# q1.net
KiCad netlist of a schematic drawn in EAGLE
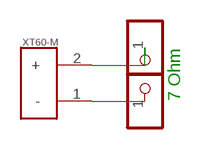
[diagram p0: schematic, sheet 1]

(export (version "E")
  (design (tool "Eeschema 10.0.6"))
  (components
    (comp (ref "J1")
      (value "XT60-M")
      (footprint "eagle-import:AMASS_XT60-M")
      (fields (field (name "MF") "AMASS"))
      (libsource (lib "eagle-import") (part "XT60-M"))
    )
    (comp (ref "JP1")
      (value "PINHD-1X1")
      (footprint "eagle-import:1X01")
      (libsource (lib "eagle-import") (part "PINHD-1X1"))
    )
    (comp (ref "JP2")
      (value "PINHD-1X1")
      (footprint "eagle-import:1X01")
      (libsource (lib "eagle-import") (part "PINHD-1X1"))
    )
  )
  (nets
    (net (code "1") (name "Net-(J1-+)") (class "Default")
      (node (ref "J1") (pin "2") (pinfunction "+_2") (pintype "passive"))
      (node (ref "JP1") (pin "1") (pinfunction "1_1") (pintype "passive"))
    )
    (net (code "2") (name "Net-(J1--)") (class "Default")
      (node (ref "J1") (pin "1") (pinfunction "-_1") (pintype "passive"))
      (node (ref "JP2") (pin "1") (pinfunction "1_1") (pintype "passive"))
    )
  )
)
